# rgb-led-cc-driver-mk-2_0.net
KiCad netlist of a schematic drawn in EAGLE
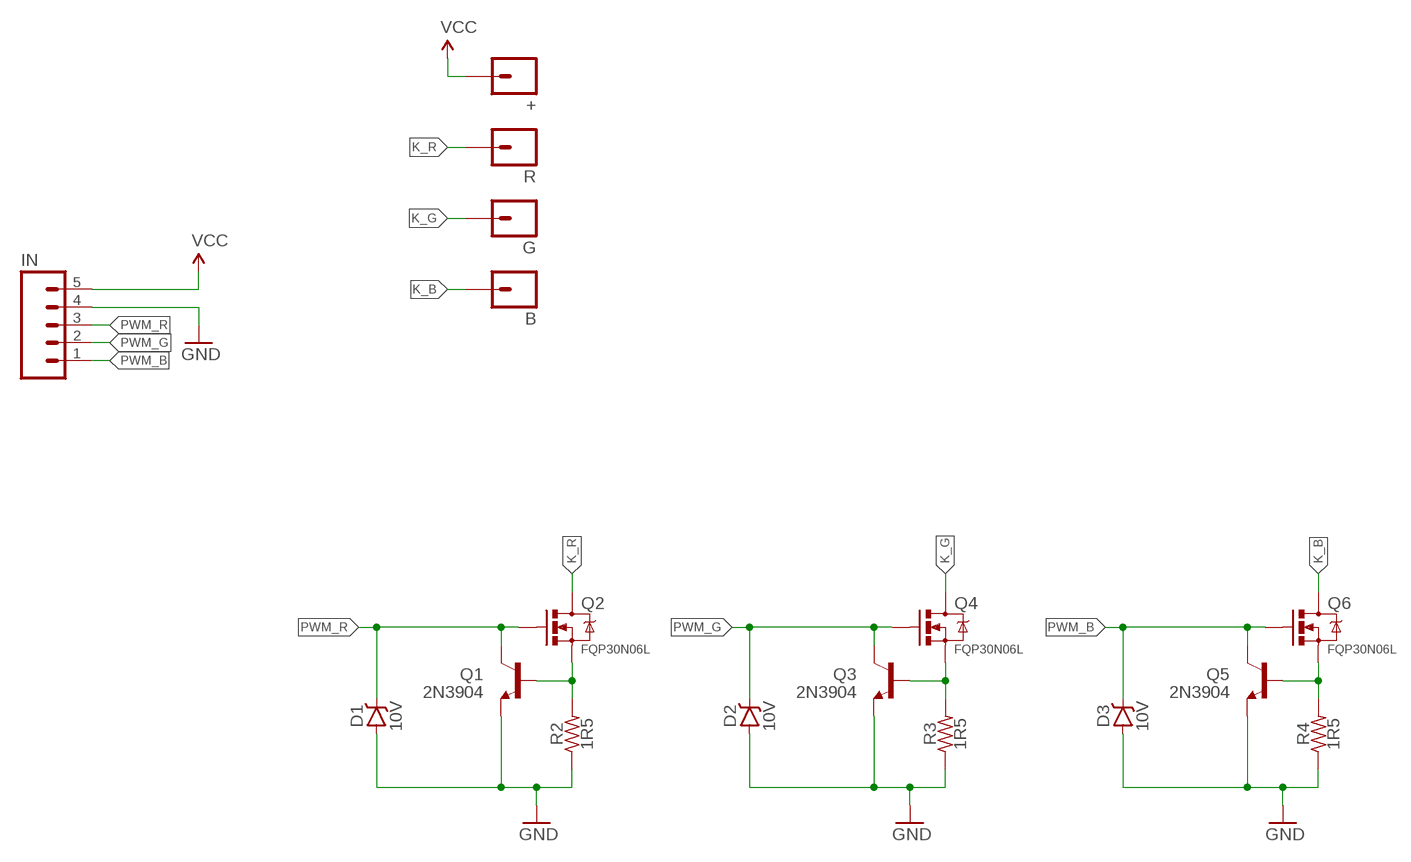
[diagram p0: schematic, sheet 1]

(export (version "E")
  (design (tool "Eeschema 10.0.6"))
  (components
    (comp (ref "+")
      (value "M01PTH_2MM")
      (footprint "eagle-import:1X01_2MM")
      (libsource (lib "eagle-import") (part "M01PTH_2MM"))
    )
    (comp (ref "B")
      (value "M01PTH_2MM")
      (footprint "eagle-import:1X01_2MM")
      (libsource (lib "eagle-import") (part "M01PTH_2MM"))
    )
    (comp (ref "D1")
      (value "10V")
      (footprint "eagle-import:DIODE-ZENNER-7.62MM")
      (libsource (lib "eagle-import") (part "DIODE-ZENER7.62MM-PTH"))
    )
    (comp (ref "D2")
      (value "10V")
      (footprint "eagle-import:DIODE-ZENNER-7.62MM")
      (libsource (lib "eagle-import") (part "DIODE-ZENER7.62MM-PTH"))
    )
    (comp (ref "D3")
      (value "10V")
      (footprint "eagle-import:DIODE-ZENNER-7.62MM")
      (libsource (lib "eagle-import") (part "DIODE-ZENER7.62MM-PTH"))
    )
    (comp (ref "G")
      (value "M01PTH_2MM")
      (footprint "eagle-import:1X01_2MM")
      (libsource (lib "eagle-import") (part "M01PTH_2MM"))
    )
    (comp (ref "IN")
      (value "M05PTH")
      (footprint "eagle-import:1X05")
      (libsource (lib "eagle-import") (part "M05PTH"))
    )
    (comp (ref "Q1")
      (value "2N3904")
      (footprint "eagle-import:TO-92-AMMO")
      (libsource (lib "eagle-import") (part "TRANSISTOR_NPNTO-92-AMMO-EBC"))
    )
    (comp (ref "Q2")
      (value "FQP30N06L")
      (footprint "eagle-import:TO220-THERMPAD-OFFSETPADS")
      (libsource (lib "eagle-import") (part "MOSFET-NCHANNELFQP30N06L-THERM-OFFSET"))
    )
    (comp (ref "Q3")
      (value "2N3904")
      (footprint "eagle-import:TO-92-AMMO")
      (libsource (lib "eagle-import") (part "TRANSISTOR_NPNTO-92-AMMO-EBC"))
    )
    (comp (ref "Q4")
      (value "FQP30N06L")
      (footprint "eagle-import:TO220-THERMPAD-OFFSETPADS")
      (libsource (lib "eagle-import") (part "MOSFET-NCHANNELFQP30N06L-THERM-OFFSET"))
    )
    (comp (ref "Q5")
      (value "2N3904")
      (footprint "eagle-import:TO-92-AMMO")
      (libsource (lib "eagle-import") (part "TRANSISTOR_NPNTO-92-AMMO-EBC"))
    )
    (comp (ref "Q6")
      (value "FQP30N06L")
      (footprint "eagle-import:TO220-THERMPAD-OFFSETPADS")
      (libsource (lib "eagle-import") (part "MOSFET-NCHANNELFQP30N06L-THERM-OFFSET"))
    )
    (comp (ref "R")
      (value "M01PTH_2MM")
      (footprint "eagle-import:1X01_2MM")
      (libsource (lib "eagle-import") (part "M01PTH_2MM"))
    )
    (comp (ref "R2")
      (value "1R5")
      (footprint "eagle-import:RESISTOR-AXIAL-PTH-10.16MM")
      (libsource (lib "eagle-import") (part "RESISTORPTH-AXIAL-10.16MM"))
    )
    (comp (ref "R3")
      (value "1R5")
      (footprint "eagle-import:RESISTOR-AXIAL-PTH-10.16MM")
      (libsource (lib "eagle-import") (part "RESISTORPTH-AXIAL-10.16MM"))
    )
    (comp (ref "R4")
      (value "1R5")
      (footprint "eagle-import:RESISTOR-AXIAL-PTH-10.16MM")
      (libsource (lib "eagle-import") (part "RESISTORPTH-AXIAL-10.16MM"))
    )
  )
  (nets
    (net (code "1") (name "GND") (class "Default")
      (node (ref "D1") (pin "A") (pinfunction "A_A") (pintype "passive"))
      (node (ref "D2") (pin "A") (pinfunction "A_A") (pintype "passive"))
      (node (ref "D3") (pin "A") (pinfunction "A_A") (pintype "passive"))
      (node (ref "IN") (pin "4") (pinfunction "4_4") (pintype "passive"))
      (node (ref "Q1") (pin "1") (pinfunction "E_1") (pintype "passive"))
      (node (ref "Q3") (pin "1") (pinfunction "E_1") (pintype "passive"))
      (node (ref "Q5") (pin "1") (pinfunction "E_1") (pintype "passive"))
      (node (ref "R2") (pin "P$1") (pinfunction "1_P$1") (pintype "passive"))
      (node (ref "R3") (pin "P$1") (pinfunction "1_P$1") (pintype "passive"))
      (node (ref "R4") (pin "P$1") (pinfunction "1_P$1") (pintype "passive"))
    )
    (net (code "2") (name "K_B") (class "Default")
      (node (ref "B") (pin "1") (pinfunction "1_1") (pintype "passive"))
      (node (ref "Q6") (pin "2@2") (pinfunction "D_2@2") (pintype "passive"))
    )
    (net (code "3") (name "K_G") (class "Default")
      (node (ref "G") (pin "1") (pinfunction "1_1") (pintype "passive"))
      (node (ref "Q4") (pin "2@2") (pinfunction "D_2@2") (pintype "passive"))
    )
    (net (code "4") (name "K_R") (class "Default")
      (node (ref "Q2") (pin "2@2") (pinfunction "D_2@2") (pintype "passive"))
      (node (ref "R") (pin "1") (pinfunction "1_1") (pintype "passive"))
    )
    (net (code "5") (name "Net-(Q1-B)") (class "Default")
      (node (ref "Q1") (pin "2") (pinfunction "B_2") (pintype "passive"))
      (node (ref "Q2") (pin "3") (pinfunction "S_3") (pintype "passive"))
      (node (ref "R2") (pin "P$2") (pinfunction "2_P$2") (pintype "passive"))
    )
    (net (code "6") (name "Net-(Q3-B)") (class "Default")
      (node (ref "Q3") (pin "2") (pinfunction "B_2") (pintype "passive"))
      (node (ref "Q4") (pin "3") (pinfunction "S_3") (pintype "passive"))
      (node (ref "R3") (pin "P$2") (pinfunction "2_P$2") (pintype "passive"))
    )
    (net (code "7") (name "Net-(Q5-B)") (class "Default")
      (node (ref "Q5") (pin "2") (pinfunction "B_2") (pintype "passive"))
      (node (ref "Q6") (pin "3") (pinfunction "S_3") (pintype "passive"))
      (node (ref "R4") (pin "P$2") (pinfunction "2_P$2") (pintype "passive"))
    )
    (net (code "8") (name "PWM_B") (class "Default")
      (node (ref "D3") (pin "K") (pinfunction "C_K") (pintype "passive"))
      (node (ref "IN") (pin "1") (pinfunction "1_1") (pintype "passive"))
      (node (ref "Q5") (pin "3") (pinfunction "C_3") (pintype "passive"))
      (node (ref "Q6") (pin "1") (pinfunction "G_1") (pintype "passive"))
    )
    (net (code "9") (name "PWM_G") (class "Default")
      (node (ref "D2") (pin "K") (pinfunction "C_K") (pintype "passive"))
      (node (ref "IN") (pin "2") (pinfunction "2_2") (pintype "passive"))
      (node (ref "Q3") (pin "3") (pinfunction "C_3") (pintype "passive"))
      (node (ref "Q4") (pin "1") (pinfunction "G_1") (pintype "passive"))
    )
    (net (code "10") (name "PWM_R") (class "Default")
      (node (ref "D1") (pin "K") (pinfunction "C_K") (pintype "passive"))
      (node (ref "IN") (pin "3") (pinfunction "3_3") (pintype "passive"))
      (node (ref "Q1") (pin "3") (pinfunction "C_3") (pintype "passive"))
      (node (ref "Q2") (pin "1") (pinfunction "G_1") (pintype "passive"))
    )
    (net (code "11") (name "VCC") (class "Default")
      (node (ref "+") (pin "1") (pinfunction "1_1") (pintype "passive"))
      (node (ref "IN") (pin "5") (pinfunction "5_5") (pintype "passive"))
    )
  )
)
